# BusCon40.net
KiCad netlist of a schematic drawn in EAGLE
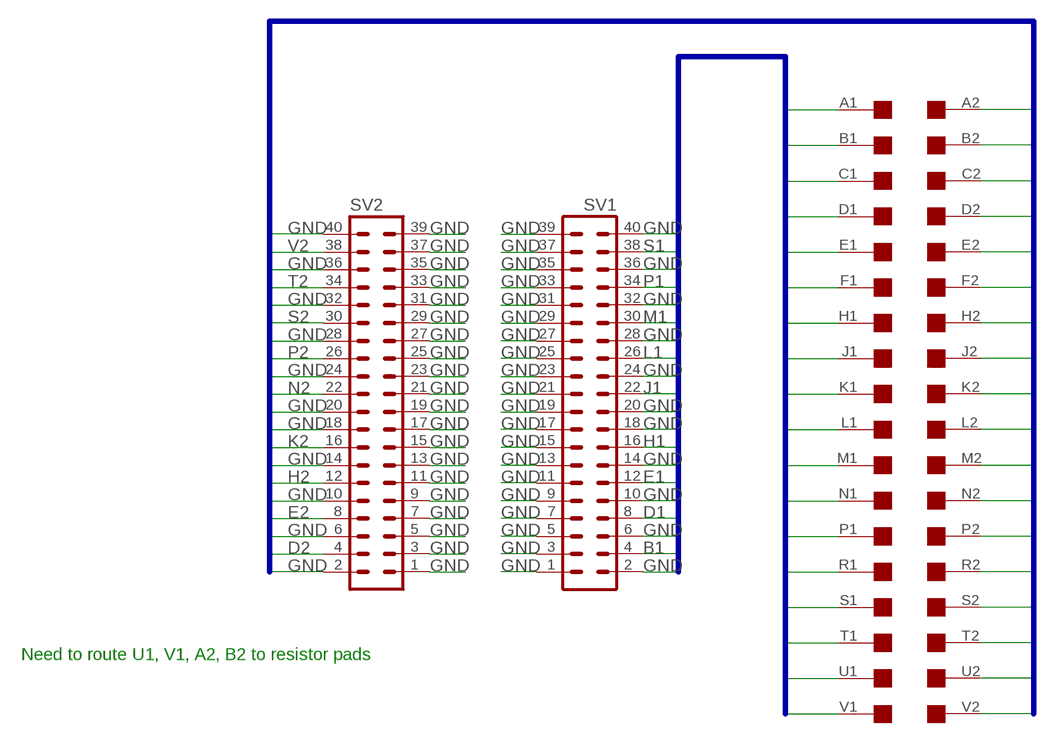
[diagram p0: schematic, sheet 1]

(export (version "E")
  (design (tool "Eeschema 10.0.6"))
  (components
    (comp (ref "SV1")
      (value "MA20-2W")
      (footprint "eagle-import:MA20-2W")
      (libsource (lib "eagle-import") (part "MA20-2W"))
    )
    (comp (ref "SV2")
      (value "MA20-2W")
      (footprint "eagle-import:MA20-2W")
      (libsource (lib "eagle-import") (part "MA20-2W"))
    )
    (comp (ref "U$1")
      (value "DEC-FLIPCHIP")
      (footprint "eagle-import:DEC-FLIPCHIP")
      (libsource (lib "eagle-import") (part "DEC-FLIPCHIP"))
    )
  )
  (nets
    (net (code "1") (name "/B1") (class "Default")
      (node (ref "SV1") (pin "4") (pinfunction "4_4") (pintype "passive"))
      (node (ref "U$1") (pin "B1") (pinfunction "B1_B1") (pintype "passive"))
    )
    (net (code "2") (name "/D1") (class "Default")
      (node (ref "SV1") (pin "8") (pinfunction "8_8") (pintype "passive"))
      (node (ref "U$1") (pin "D1") (pinfunction "D1_D1") (pintype "passive"))
    )
    (net (code "3") (name "/D2") (class "Default")
      (node (ref "SV2") (pin "4") (pinfunction "4_4") (pintype "passive"))
      (node (ref "U$1") (pin "D2") (pinfunction "D2_D2") (pintype "passive"))
    )
    (net (code "4") (name "/E1") (class "Default")
      (node (ref "SV1") (pin "12") (pinfunction "12_12") (pintype "passive"))
      (node (ref "U$1") (pin "E1") (pinfunction "E1_E1") (pintype "passive"))
    )
    (net (code "5") (name "/E2") (class "Default")
      (node (ref "SV2") (pin "8") (pinfunction "8_8") (pintype "passive"))
      (node (ref "U$1") (pin "E2") (pinfunction "E2_E2") (pintype "passive"))
    )
    (net (code "6") (name "/GND") (class "Default")
      (node (ref "SV1") (pin "1") (pinfunction "1_1") (pintype "passive"))
      (node (ref "SV1") (pin "10") (pinfunction "10_10") (pintype "passive"))
      (node (ref "SV1") (pin "11") (pinfunction "11_11") (pintype "passive"))
      (node (ref "SV1") (pin "13") (pinfunction "13_13") (pintype "passive"))
      (node (ref "SV1") (pin "14") (pinfunction "14_14") (pintype "passive"))
      (node (ref "SV1") (pin "15") (pinfunction "15_15") (pintype "passive"))
      (node (ref "SV1") (pin "17") (pinfunction "17_17") (pintype "passive"))
      (node (ref "SV1") (pin "18") (pinfunction "18_18") (pintype "passive"))
      (node (ref "SV1") (pin "19") (pinfunction "19_19") (pintype "passive"))
      (node (ref "SV1") (pin "2") (pinfunction "2_2") (pintype "passive"))
      (node (ref "SV1") (pin "20") (pinfunction "20_20") (pintype "passive"))
      (node (ref "SV1") (pin "21") (pinfunction "21_21") (pintype "passive"))
      (node (ref "SV1") (pin "23") (pinfunction "23_23") (pintype "passive"))
      (node (ref "SV1") (pin "24") (pinfunction "24_24") (pintype "passive"))
      (node (ref "SV1") (pin "25") (pinfunction "25_25") (pintype "passive"))
      (node (ref "SV1") (pin "27") (pinfunction "27_27") (pintype "passive"))
      (node (ref "SV1") (pin "28") (pinfunction "28_28") (pintype "passive"))
      (node (ref "SV1") (pin "29") (pinfunction "29_29") (pintype "passive"))
      (node (ref "SV1") (pin "3") (pinfunction "3_3") (pintype "passive"))
      (node (ref "SV1") (pin "31") (pinfunction "31_31") (pintype "passive"))
      (node (ref "SV1") (pin "32") (pinfunction "32_32") (pintype "passive"))
      (node (ref "SV1") (pin "33") (pinfunction "33_33") (pintype "passive"))
      (node (ref "SV1") (pin "35") (pinfunction "35_35") (pintype "passive"))
      (node (ref "SV1") (pin "36") (pinfunction "36_36") (pintype "passive"))
      (node (ref "SV1") (pin "37") (pinfunction "37_37") (pintype "passive"))
      (node (ref "SV1") (pin "39") (pinfunction "39_39") (pintype "passive"))
      (node (ref "SV1") (pin "40") (pinfunction "40_40") (pintype "passive"))
      (node (ref "SV1") (pin "5") (pinfunction "5_5") (pintype "passive"))
      (node (ref "SV1") (pin "6") (pinfunction "6_6") (pintype "passive"))
      (node (ref "SV1") (pin "7") (pinfunction "7_7") (pintype "passive"))
      (node (ref "SV1") (pin "9") (pinfunction "9_9") (pintype "passive"))
      (node (ref "SV2") (pin "1") (pinfunction "1_1") (pintype "passive"))
      (node (ref "SV2") (pin "10") (pinfunction "10_10") (pintype "passive"))
      (node (ref "SV2") (pin "11") (pinfunction "11_11") (pintype "passive"))
      (node (ref "SV2") (pin "13") (pinfunction "13_13") (pintype "passive"))
      (node (ref "SV2") (pin "14") (pinfunction "14_14") (pintype "passive"))
      (node (ref "SV2") (pin "15") (pinfunction "15_15") (pintype "passive"))
      (node (ref "SV2") (pin "17") (pinfunction "17_17") (pintype "passive"))
      (node (ref "SV2") (pin "18") (pinfunction "18_18") (pintype "passive"))
      (node (ref "SV2") (pin "19") (pinfunction "19_19") (pintype "passive"))
      (node (ref "SV2") (pin "2") (pinfunction "2_2") (pintype "passive"))
      (node (ref "SV2") (pin "20") (pinfunction "20_20") (pintype "passive"))
      (node (ref "SV2") (pin "21") (pinfunction "21_21") (pintype "passive"))
      (node (ref "SV2") (pin "23") (pinfunction "23_23") (pintype "passive"))
      (node (ref "SV2") (pin "24") (pinfunction "24_24") (pintype "passive"))
      (node (ref "SV2") (pin "25") (pinfunction "25_25") (pintype "passive"))
      (node (ref "SV2") (pin "27") (pinfunction "27_27") (pintype "passive"))
      (node (ref "SV2") (pin "28") (pinfunction "28_28") (pintype "passive"))
      (node (ref "SV2") (pin "29") (pinfunction "29_29") (pintype "passive"))
      (node (ref "SV2") (pin "3") (pinfunction "3_3") (pintype "passive"))
      (node (ref "SV2") (pin "31") (pinfunction "31_31") (pintype "passive"))
      (node (ref "SV2") (pin "32") (pinfunction "32_32") (pintype "passive"))
      (node (ref "SV2") (pin "33") (pinfunction "33_33") (pintype "passive"))
      (node (ref "SV2") (pin "35") (pinfunction "35_35") (pintype "passive"))
      (node (ref "SV2") (pin "36") (pinfunction "36_36") (pintype "passive"))
      (node (ref "SV2") (pin "37") (pinfunction "37_37") (pintype "passive"))
      (node (ref "SV2") (pin "39") (pinfunction "39_39") (pintype "passive"))
      (node (ref "SV2") (pin "40") (pinfunction "40_40") (pintype "passive"))
      (node (ref "SV2") (pin "5") (pinfunction "5_5") (pintype "passive"))
      (node (ref "SV2") (pin "6") (pinfunction "6_6") (pintype "passive"))
      (node (ref "SV2") (pin "7") (pinfunction "7_7") (pintype "passive"))
      (node (ref "SV2") (pin "9") (pinfunction "9_9") (pintype "passive"))
      (node (ref "U$1") (pin "A1") (pinfunction "A1_A1") (pintype "passive"))
      (node (ref "U$1") (pin "C1") (pinfunction "C1_C1") (pintype "passive"))
      (node (ref "U$1") (pin "C2") (pinfunction "C2_C2") (pintype "passive"))
      (node (ref "U$1") (pin "F1") (pinfunction "F1_F1") (pintype "passive"))
      (node (ref "U$1") (pin "F2") (pinfunction "F2_F2") (pintype "passive"))
      (node (ref "U$1") (pin "J2") (pinfunction "J2_J2") (pintype "passive"))
      (node (ref "U$1") (pin "K1") (pinfunction "K1_K1") (pintype "passive"))
      (node (ref "U$1") (pin "L2") (pinfunction "L2_L2") (pintype "passive"))
      (node (ref "U$1") (pin "M2") (pinfunction "M2_M2") (pintype "passive"))
      (node (ref "U$1") (pin "N1") (pinfunction "N1_N1") (pintype "passive"))
      (node (ref "U$1") (pin "R1") (pinfunction "R1_R1") (pintype "passive"))
      (node (ref "U$1") (pin "R2") (pinfunction "R2_R2") (pintype "passive"))
      (node (ref "U$1") (pin "T1") (pinfunction "T1_T1") (pintype "passive"))
      (node (ref "U$1") (pin "U2") (pinfunction "U2_U2") (pintype "passive"))
    )
    (net (code "7") (name "/H1") (class "Default")
      (node (ref "SV1") (pin "16") (pinfunction "16_16") (pintype "passive"))
      (node (ref "U$1") (pin "H1") (pinfunction "H1_H1") (pintype "passive"))
    )
    (net (code "8") (name "/H2") (class "Default")
      (node (ref "SV2") (pin "12") (pinfunction "12_12") (pintype "passive"))
      (node (ref "U$1") (pin "H2") (pinfunction "H2_H2") (pintype "passive"))
    )
    (net (code "9") (name "/J1") (class "Default")
      (node (ref "SV1") (pin "22") (pinfunction "22_22") (pintype "passive"))
      (node (ref "U$1") (pin "J1") (pinfunction "J1_J1") (pintype "passive"))
    )
    (net (code "10") (name "/K2") (class "Default")
      (node (ref "SV2") (pin "16") (pinfunction "16_16") (pintype "passive"))
      (node (ref "U$1") (pin "K2") (pinfunction "K2_K2") (pintype "passive"))
    )
    (net (code "11") (name "/L1") (class "Default")
      (node (ref "SV1") (pin "26") (pinfunction "26_26") (pintype "passive"))
      (node (ref "U$1") (pin "L1") (pinfunction "L1_L1") (pintype "passive"))
    )
    (net (code "12") (name "/M1") (class "Default")
      (node (ref "SV1") (pin "30") (pinfunction "30_30") (pintype "passive"))
      (node (ref "U$1") (pin "M1") (pinfunction "M1_M1") (pintype "passive"))
    )
    (net (code "13") (name "/N2") (class "Default")
      (node (ref "SV2") (pin "22") (pinfunction "22_22") (pintype "passive"))
      (node (ref "U$1") (pin "N2") (pinfunction "N2_N2") (pintype "passive"))
    )
    (net (code "14") (name "/P1") (class "Default")
      (node (ref "SV1") (pin "34") (pinfunction "34_34") (pintype "passive"))
      (node (ref "U$1") (pin "P1") (pinfunction "P1_P1") (pintype "passive"))
    )
    (net (code "15") (name "/P2") (class "Default")
      (node (ref "SV2") (pin "26") (pinfunction "26_26") (pintype "passive"))
      (node (ref "U$1") (pin "P2") (pinfunction "P2_P2") (pintype "passive"))
    )
    (net (code "16") (name "/S1") (class "Default")
      (node (ref "SV1") (pin "38") (pinfunction "38_38") (pintype "passive"))
      (node (ref "U$1") (pin "S1") (pinfunction "S1_S1") (pintype "passive"))
    )
    (net (code "17") (name "/S2") (class "Default")
      (node (ref "SV2") (pin "30") (pinfunction "30_30") (pintype "passive"))
      (node (ref "U$1") (pin "S2") (pinfunction "S2_S2") (pintype "passive"))
    )
    (net (code "18") (name "/T2") (class "Default")
      (node (ref "SV2") (pin "34") (pinfunction "34_34") (pintype "passive"))
      (node (ref "U$1") (pin "T2") (pinfunction "T2_T2") (pintype "passive"))
    )
    (net (code "19") (name "/V2") (class "Default")
      (node (ref "SV2") (pin "38") (pinfunction "38_38") (pintype "passive"))
      (node (ref "U$1") (pin "V2") (pinfunction "V2_V2") (pintype "passive"))
    )
    (net (code "20") (name "unconnected-(U$1-PadA2)") (class "Default")
      (node (ref "U$1") (pin "A2") (pinfunction "A2_A2") (pintype "passive"))
    )
    (net (code "21") (name "unconnected-(U$1-PadB2)") (class "Default")
      (node (ref "U$1") (pin "B2") (pinfunction "B2_B2") (pintype "passive"))
    )
    (net (code "22") (name "unconnected-(U$1-PadU1)") (class "Default")
      (node (ref "U$1") (pin "U1") (pinfunction "U1_U1") (pintype "passive"))
    )
    (net (code "23") (name "unconnected-(U$1-PadV1)") (class "Default")
      (node (ref "U$1") (pin "V1") (pinfunction "V1_V1") (pintype "passive"))
    )
  )
)
